# Radio.net
KiCad netlist of a schematic drawn in Altium Designer
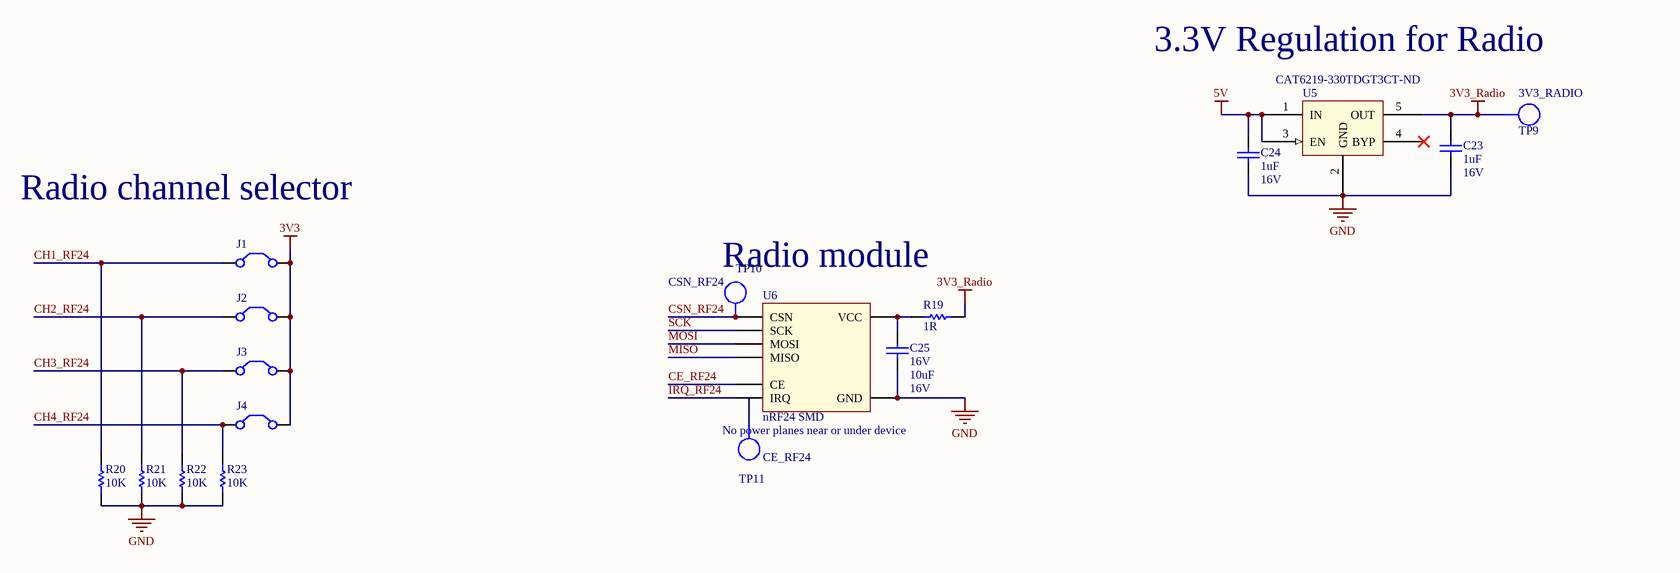
[diagram p0: Radio.SchDoc]

(export (version "E")
  (design (tool "Eeschema 10.0.6"))
  (components
    (comp (ref "C23")
      (value "1uF")
      (footprint "CAPC1608L")
      (description "CAP CER 1uF Y5V -20% +80% 16V 0603")
      (fields (field (name "MAX VOLTAGE") "16V"))
      (libsource (lib "ECE AD19Components_19V1") (part "CC_1uF_0603"))
    )
    (comp (ref "C24")
      (value "1uF")
      (footprint "CAPC1608L")
      (description "CAP CER 1uF Y5V -20% +80% 16V 0603")
      (fields (field (name "MAX VOLTAGE") "16V"))
      (libsource (lib "ECE AD19Components_19V1") (part "CC_1uF_0603"))
    )
    (comp (ref "C25")
      (value "10uF")
      (footprint "CAPC2012L")
      (description "CAP CER 10uF X5R 16V 0805")
      (fields
        (field (name "MANUFACTURER") "Samsung Electro-Mechanics")
        (field (name "MANUFACTURER PART NUMBER") "CL21A106KOQNNWE")
        (field (name "VOLTAGE - RATED") "16V")
        (field (name "MAX VOLTAGE") "16V")
      )
      (libsource (lib "ENCE461AD19_19V2") (part "CC_10uF_16V_0805"))
    )
    (comp (ref "J1")
      (value "100Mil Jumper")
      (footprint "JMP2.54")
      (description "2.54mm Jumper Thru Hole")
      (libsource (lib "ECE AD19Components_19V1") (part "TP_JUMPER"))
    )
    (comp (ref "J2")
      (value "100Mil Jumper")
      (footprint "JMP2.54")
      (description "2.54mm Jumper Thru Hole")
      (libsource (lib "ECE AD19Components_19V1") (part "TP_JUMPER"))
    )
    (comp (ref "J3")
      (value "100Mil Jumper")
      (footprint "JMP2.54")
      (description "2.54mm Jumper Thru Hole")
      (libsource (lib "ECE AD19Components_19V1") (part "TP_JUMPER"))
    )
    (comp (ref "J4")
      (value "100Mil Jumper")
      (footprint "JMP2.54")
      (description "2.54mm Jumper Thru Hole")
      (libsource (lib "ECE AD19Components_19V1") (part "TP_JUMPER"))
    )
    (comp (ref "R19")
      (value "1R")
      (footprint "RESC3216L")
      (description "RES 1R OHM 1/4W 5% 1206 SMD")
      (libsource (lib "ECE AD19Components_19V1") (part "RT_1R"))
    )
    (comp (ref "R20")
      (value "10K")
      (footprint "RESC1608L")
      (description "RES 10.0K OHM 1/10W 5% 0603 SMD")
      (libsource (lib "ECE AD19Components_19V1") (part "RS_10K"))
    )
    (comp (ref "R21")
      (value "10K")
      (footprint "RESC1608L")
      (description "RES 10.0K OHM 1/10W 5% 0603 SMD")
      (libsource (lib "ECE AD19Components_19V1") (part "RS_10K"))
    )
    (comp (ref "R22")
      (value "10K")
      (footprint "RESC1608L")
      (description "RES 10.0K OHM 1/10W 5% 0603 SMD")
      (libsource (lib "ECE AD19Components_19V1") (part "RS_10K"))
    )
    (comp (ref "R23")
      (value "10K")
      (footprint "RESC1608L")
      (description "RES 10.0K OHM 1/10W 5% 0603 SMD")
      (libsource (lib "ECE AD19Components_19V1") (part "RS_10K"))
    )
    (comp (ref "TP9")
      (value "3V3_RADIO")
      (footprint "TP_1206")
      (description "Test-Point 3.3x1.6x2.1mm SMD")
      (fields
        (field (name "MANUFACTURER") "Harwin Inc")
        (field (name "MANUFACTURER PART NUMBER") "S1751-46R")
      )
      (libsource (lib "ECE AD19Components_19V1") (part "TP_1206"))
    )
    (comp (ref "TP10")
      (value "CSN_RF24")
      (footprint "TP_1206")
      (description "Test-Point 3.3x1.6x2.1mm SMD")
      (fields
        (field (name "MANUFACTURER") "Harwin Inc")
        (field (name "MANUFACTURER PART NUMBER") "S1751-46R")
      )
      (libsource (lib "ECE AD19Components_19V1") (part "TP_1206"))
    )
    (comp (ref "TP11")
      (value "CE_RF24")
      (footprint "TP_1206")
      (description "Test-Point 3.3x1.6x2.1mm SMD")
      (fields
        (field (name "MANUFACTURER") "Harwin Inc")
        (field (name "MANUFACTURER PART NUMBER") "S1751-46R")
      )
      (libsource (lib "ECE AD19Components_19V1") (part "TP_1206"))
    )
    (comp (ref "U5")
      (value "CAT6219-330TDGT3")
      (footprint "SOT95P280X145-5N")
      (description "IC REG LIN 3.3V 500MA TSOT23-5")
      (fields
        (field (name "BASE PART NUMBER") "CAT6219")
        (field (name "SUPPLIER PART NUMBER") "CAT6219-330TDGT3CT-ND")
      )
      (libsource (lib "ENCE461AD19_19V2") (part "SV_CAT6219-330TDGT3"))
    )
    (comp (ref "U6")
      (value "nRF24 SMD")
      (footprint "NRF24")
      (description "nRF24 SMD Module")
      (fields (field (name "WARNING") "No power planes near or under device"))
      (libsource (lib "ENCE461AD19_19V2") (part "NRF24"))
    )
  )
  (nets
    (net (code "1") (name "/CE_RF24") (class "Default")
      (node (ref "U6") (pin "3") (pinfunction "CE_3") (pintype "passive"))
    )
    (net (code "2") (name "/CH1_RF24") (class "Default")
      (node (ref "J1") (pin "1") (pinfunction "C1_1") (pintype "passive"))
      (node (ref "R20") (pin "2") (pinfunction "2_2") (pintype "passive"))
    )
    (net (code "3") (name "/CH2_RF24") (class "Default")
      (node (ref "J2") (pin "1") (pinfunction "C1_1") (pintype "passive"))
      (node (ref "R21") (pin "2") (pinfunction "2_2") (pintype "passive"))
    )
    (net (code "4") (name "/CH3_RF24") (class "Default")
      (node (ref "J3") (pin "1") (pinfunction "C1_1") (pintype "passive"))
      (node (ref "R22") (pin "2") (pinfunction "2_2") (pintype "passive"))
    )
    (net (code "5") (name "/CH4_RF24") (class "Default")
      (node (ref "J4") (pin "1") (pinfunction "C1_1") (pintype "passive"))
      (node (ref "R23") (pin "2") (pinfunction "2_2") (pintype "passive"))
    )
    (net (code "6") (name "/CSN_RF24") (class "Default")
      (node (ref "TP10") (pin "1") (pinfunction "1_1") (pintype "passive"))
      (node (ref "U6") (pin "4") (pinfunction "CSN_4") (pintype "passive"))
    )
    (net (code "7") (name "/IRQ_RF24") (class "Default")
      (node (ref "U6") (pin "8") (pinfunction "IRQ_8") (pintype "passive"))
    )
    (net (code "8") (name "/MISO") (class "Default")
      (node (ref "U6") (pin "7") (pinfunction "MISO_7") (pintype "passive"))
    )
    (net (code "9") (name "/MOSI") (class "Default")
      (node (ref "U6") (pin "6") (pinfunction "MOSI_6") (pintype "passive"))
    )
    (net (code "10") (name "/SCK") (class "Default")
      (node (ref "U6") (pin "5") (pinfunction "SCK_5") (pintype "passive"))
    )
    (net (code "11") (name "3V3") (class "Default")
      (node (ref "J1") (pin "2") (pinfunction "C2_2") (pintype "passive"))
      (node (ref "J2") (pin "2") (pinfunction "C2_2") (pintype "passive"))
      (node (ref "J3") (pin "2") (pinfunction "C2_2") (pintype "passive"))
      (node (ref "J4") (pin "2") (pinfunction "C2_2") (pintype "passive"))
    )
    (net (code "12") (name "3V3_Radio") (class "Default")
      (node (ref "C23") (pin "2") (pinfunction "2_2") (pintype "passive"))
      (node (ref "R19") (pin "2") (pinfunction "2_2") (pintype "passive"))
      (node (ref "TP9") (pin "1") (pinfunction "1_1") (pintype "passive"))
      (node (ref "U5") (pin "5") (pinfunction "OUT_5") (pintype "power_in"))
    )
    (net (code "13") (name "5V") (class "Default")
      (node (ref "C24") (pin "2") (pinfunction "2_2") (pintype "passive"))
      (node (ref "U5") (pin "1") (pinfunction "IN_1") (pintype "power_in"))
      (node (ref "U5") (pin "3") (pinfunction "EN_3") (pintype "input"))
    )
    (net (code "14") (name "GND") (class "Default")
      (node (ref "C23") (pin "1") (pinfunction "1_1") (pintype "passive"))
      (node (ref "C24") (pin "1") (pinfunction "1_1") (pintype "passive"))
      (node (ref "C25") (pin "1") (pinfunction "1_1") (pintype "passive"))
      (node (ref "R20") (pin "1") (pinfunction "1_1") (pintype "passive"))
      (node (ref "R21") (pin "1") (pinfunction "1_1") (pintype "passive"))
      (node (ref "R22") (pin "1") (pinfunction "1_1") (pintype "passive"))
      (node (ref "R23") (pin "1") (pinfunction "1_1") (pintype "passive"))
      (node (ref "U5") (pin "2") (pinfunction "GND_2") (pintype "power_in"))
      (node (ref "U6") (pin "2") (pinfunction "GND_2") (pintype "passive"))
    )
    (net (code "15") (name "Net-(U6-VCC)") (class "Default")
      (node (ref "C25") (pin "2") (pinfunction "2_2") (pintype "passive"))
      (node (ref "R19") (pin "1") (pinfunction "1_1") (pintype "passive"))
      (node (ref "U6") (pin "1") (pinfunction "VCC_1") (pintype "passive"))
    )
    (net (code "16") (name "unconnected-(TP11-Pad1)") (class "Default")
      (node (ref "TP11") (pin "1") (pinfunction "1_1") (pintype "passive"))
    )
    (net (code "17") (name "unconnected-(U5-BYP-Pad4)") (class "Default")
      (node (ref "U5") (pin "4") (pinfunction "BYP_4") (pintype "passive+no_connect"))
    )
  )
)
